# pong.net
KiCad netlist of a schematic drawn in EAGLE
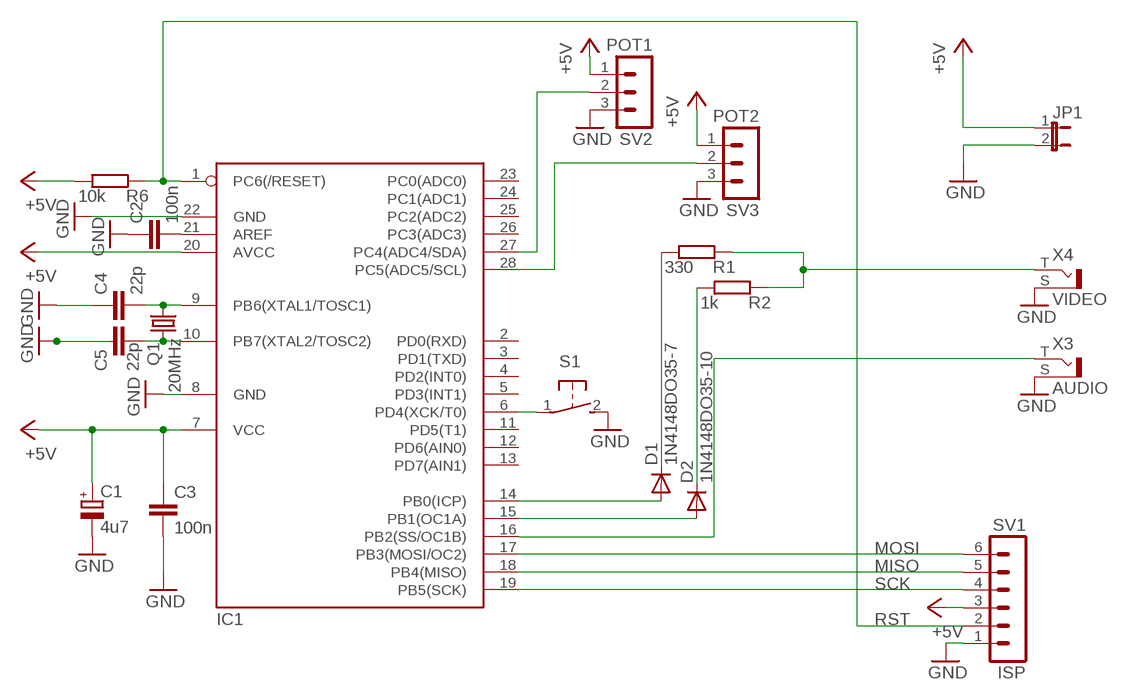
[diagram p0: schematic, sheet 1]

(export (version "E")
  (design (tool "Eeschema 10.0.6"))
  (components
    (comp (ref "C1")
      (value "4u7")
      (footprint "eagle-import:TT5D7")
      (libsource (lib "eagle-import") (part "CPOL-EUTT5D7"))
    )
    (comp (ref "C2")
      (value "100n")
      (footprint "eagle-import:C025-024X044")
      (libsource (lib "eagle-import") (part "C-EU025-024X044"))
    )
    (comp (ref "C3")
      (value "100n")
      (footprint "eagle-import:C025-024X044")
      (libsource (lib "eagle-import") (part "C-EU025-024X044"))
    )
    (comp (ref "C4")
      (value "22p")
      (footprint "eagle-import:C025-024X044")
      (libsource (lib "eagle-import") (part "C-EU025-024X044"))
    )
    (comp (ref "C5")
      (value "22p")
      (footprint "eagle-import:C050-025X075")
      (libsource (lib "eagle-import") (part "C-EU050-025X075"))
    )
    (comp (ref "D1")
      (value "1N4148DO35-7")
      (footprint "eagle-import:DO35-7")
      (libsource (lib "eagle-import") (part "1N4148DO35-7"))
    )
    (comp (ref "D2")
      (value "1N4148DO35-10")
      (footprint "eagle-import:DO35-10")
      (libsource (lib "eagle-import") (part "1N4148DO35-10"))
    )
    (comp (ref "IC1")
      (value "MEGA8-P")
      (footprint "eagle-import:DIL28-3")
      (libsource (lib "eagle-import") (part "MEGA8-P"))
    )
    (comp (ref "JP1")
      (value "JP1E")
      (footprint "eagle-import:JP1")
      (libsource (lib "eagle-import") (part "JP1E"))
    )
    (comp (ref "Q1")
      (value "20MHz")
      (footprint "eagle-import:TC26V")
      (libsource (lib "eagle-import") (part "CRYSTALTC26V"))
    )
    (comp (ref "R1")
      (value "330")
      (footprint "eagle-import:0204_5")
      (libsource (lib "eagle-import") (part "R-EU_0204/5"))
    )
    (comp (ref "R2")
      (value "1k")
      (footprint "eagle-import:0204_7")
      (libsource (lib "eagle-import") (part "R-EU_0204/7"))
    )
    (comp (ref "R6")
      (value "10k")
      (footprint "eagle-import:0207_15")
      (libsource (lib "eagle-import") (part "R-EU_0207/15"))
    )
    (comp (ref "S1")
      (value "31-XX")
      (footprint "eagle-import:B3F-31XX")
      (fields (field (name "MPN") "B3F-3100"))
      (libsource (lib "eagle-import") (part "31-XX"))
    )
    (comp (ref "SV1")
      (value "ISP")
      (footprint "eagle-import:MA06-1")
      (libsource (lib "eagle-import") (part "MA06-1"))
    )
    (comp (ref "SV2")
      (value "POT1")
      (footprint "eagle-import:MA03-1")
      (libsource (lib "eagle-import") (part "MA03-1"))
    )
    (comp (ref "SV3")
      (value "POT2")
      (footprint "eagle-import:MA03-1")
      (libsource (lib "eagle-import") (part "MA03-1"))
    )
    (comp (ref "X3")
      (value "AUDIO")
      (footprint "eagle-import:WBTOR1")
      (fields (field (name "MPN") "WBTOR 1 BLACK"))
      (libsource (lib "eagle-import") (part "WBTOR1"))
    )
    (comp (ref "X4")
      (value "VIDEO")
      (footprint "eagle-import:WBTOR1")
      (fields (field (name "MPN") "WBTOR 1 BLACK"))
      (libsource (lib "eagle-import") (part "WBTOR1"))
    )
  )
  (nets
    (net (code "1") (name "+5V") (class "Default")
      (node (ref "C1") (pin "+") (pinfunction "+_+") (pintype "passive"))
      (node (ref "C3") (pin "1") (pinfunction "1_1") (pintype "passive"))
      (node (ref "IC1") (pin "20") (pinfunction "AVCC_20") (pintype "power_in"))
      (node (ref "IC1") (pin "7") (pinfunction "VCC_7") (pintype "power_in"))
      (node (ref "JP1") (pin "1") (pinfunction "1_1") (pintype "passive"))
      (node (ref "R6") (pin "1") (pinfunction "1_1") (pintype "passive"))
      (node (ref "SV1") (pin "3") (pinfunction "3_3") (pintype "passive"))
      (node (ref "SV2") (pin "1") (pinfunction "1_1") (pintype "passive"))
      (node (ref "SV3") (pin "1") (pinfunction "1_1") (pintype "passive"))
    )
    (net (code "2") (name "/MISO") (class "Default")
      (node (ref "IC1") (pin "18") (pinfunction "PB4(MISO)_18") (pintype "bidirectional"))
      (node (ref "SV1") (pin "5") (pinfunction "5_5") (pintype "passive"))
    )
    (net (code "3") (name "/MOSI") (class "Default")
      (node (ref "IC1") (pin "17") (pinfunction "PB3(MOSI/OC2)_17") (pintype "bidirectional"))
      (node (ref "SV1") (pin "6") (pinfunction "6_6") (pintype "passive"))
    )
    (net (code "4") (name "/RST") (class "Default")
      (node (ref "IC1") (pin "1") (pinfunction "PC6(/RESET)_1") (pintype "bidirectional"))
      (node (ref "R6") (pin "2") (pinfunction "2_2") (pintype "passive"))
      (node (ref "SV1") (pin "2") (pinfunction "2_2") (pintype "passive"))
    )
    (net (code "5") (name "/SCK") (class "Default")
      (node (ref "IC1") (pin "19") (pinfunction "PB5(SCK)_19") (pintype "bidirectional"))
      (node (ref "SV1") (pin "4") (pinfunction "4_4") (pintype "passive"))
    )
    (net (code "6") (name "GND") (class "Default")
      (node (ref "C1") (pin "-") (pinfunction "-_-") (pintype "passive"))
      (node (ref "C2") (pin "1") (pinfunction "1_1") (pintype "passive"))
      (node (ref "C3") (pin "2") (pinfunction "2_2") (pintype "passive"))
      (node (ref "C4") (pin "1") (pinfunction "1_1") (pintype "passive"))
      (node (ref "C5") (pin "1") (pinfunction "1_1") (pintype "passive"))
      (node (ref "IC1") (pin "22") (pinfunction "GND_22") (pintype "power_in"))
      (node (ref "IC1") (pin "8") (pinfunction "GND_8") (pintype "power_in"))
      (node (ref "JP1") (pin "2") (pinfunction "2_2") (pintype "passive"))
      (node (ref "S1") (pin "2") (pinfunction "S_2") (pintype "passive"))
      (node (ref "SV1") (pin "1") (pinfunction "1_1") (pintype "passive"))
      (node (ref "SV2") (pin "3") (pinfunction "3_3") (pintype "passive"))
      (node (ref "SV3") (pin "3") (pinfunction "3_3") (pintype "passive"))
      (node (ref "X3") (pin "S") (pinfunction "S_S") (pintype "passive"))
      (node (ref "X4") (pin "S") (pinfunction "S_S") (pintype "passive"))
    )
    (net (code "7") (name "Net-(D1-PadC)") (class "Default")
      (node (ref "D1") (pin "C") (pinfunction "C_C") (pintype "passive"))
      (node (ref "R1") (pin "1") (pinfunction "1_1") (pintype "passive"))
    )
    (net (code "8") (name "Net-(D2-PadC)") (class "Default")
      (node (ref "D2") (pin "C") (pinfunction "C_C") (pintype "passive"))
      (node (ref "R2") (pin "1") (pinfunction "1_1") (pintype "passive"))
    )
    (net (code "9") (name "Net-(IC1-AREF)") (class "Default")
      (node (ref "C2") (pin "2") (pinfunction "2_2") (pintype "passive"))
      (node (ref "IC1") (pin "21") (pinfunction "AREF_21") (pintype "passive"))
    )
    (net (code "10") (name "Net-(IC1-PB0(ICP))") (class "Default")
      (node (ref "D1") (pin "A") (pinfunction "A_A") (pintype "passive"))
      (node (ref "IC1") (pin "14") (pinfunction "PB0(ICP)_14") (pintype "bidirectional"))
    )
    (net (code "11") (name "Net-(IC1-PB1(OC1A))") (class "Default")
      (node (ref "D2") (pin "A") (pinfunction "A_A") (pintype "passive"))
      (node (ref "IC1") (pin "15") (pinfunction "PB1(OC1A)_15") (pintype "bidirectional"))
    )
    (net (code "12") (name "Net-(IC1-PB2(SS{slash}OC1B))") (class "Default")
      (node (ref "IC1") (pin "16") (pinfunction "PB2(SS/OC1B)_16") (pintype "bidirectional"))
      (node (ref "X3") (pin "T") (pinfunction "T_T") (pintype "passive"))
    )
    (net (code "13") (name "Net-(IC1-PB6(XTAL1{slash}TOSC1))") (class "Default")
      (node (ref "C4") (pin "2") (pinfunction "2_2") (pintype "passive"))
      (node (ref "IC1") (pin "9") (pinfunction "PB6(XTAL1/TOSC1)_9") (pintype "bidirectional"))
      (node (ref "Q1") (pin "2") (pinfunction "2_2") (pintype "passive"))
    )
    (net (code "14") (name "Net-(IC1-PB7(XTAL2{slash}TOSC2))") (class "Default")
      (node (ref "C5") (pin "2") (pinfunction "2_2") (pintype "passive"))
      (node (ref "IC1") (pin "10") (pinfunction "PB7(XTAL2/TOSC2)_10") (pintype "bidirectional"))
      (node (ref "Q1") (pin "1") (pinfunction "1_1") (pintype "passive"))
    )
    (net (code "15") (name "Net-(IC1-PC4(ADC4{slash}SDA))") (class "Default")
      (node (ref "IC1") (pin "27") (pinfunction "PC4(ADC4/SDA)_27") (pintype "bidirectional"))
      (node (ref "SV2") (pin "2") (pinfunction "2_2") (pintype "passive"))
    )
    (net (code "16") (name "Net-(IC1-PC5(ADC5{slash}SCL))") (class "Default")
      (node (ref "IC1") (pin "28") (pinfunction "PC5(ADC5/SCL)_28") (pintype "bidirectional"))
      (node (ref "SV3") (pin "2") (pinfunction "2_2") (pintype "passive"))
    )
    (net (code "17") (name "Net-(IC1-PD4(XCK{slash}T0))") (class "Default")
      (node (ref "IC1") (pin "6") (pinfunction "PD4(XCK/T0)_6") (pintype "bidirectional"))
      (node (ref "S1") (pin "1") (pinfunction "P_1") (pintype "passive"))
    )
    (net (code "18") (name "Net-(R1-Pad2)") (class "Default")
      (node (ref "R1") (pin "2") (pinfunction "2_2") (pintype "passive"))
      (node (ref "R2") (pin "2") (pinfunction "2_2") (pintype "passive"))
      (node (ref "X4") (pin "T") (pinfunction "T_T") (pintype "passive"))
    )
    (net (code "19") (name "unconnected-(IC1-PC0(ADC0)-Pad23)") (class "Default")
      (node (ref "IC1") (pin "23") (pinfunction "PC0(ADC0)_23") (pintype "bidirectional"))
    )
    (net (code "20") (name "unconnected-(IC1-PC1(ADC1)-Pad24)") (class "Default")
      (node (ref "IC1") (pin "24") (pinfunction "PC1(ADC1)_24") (pintype "bidirectional"))
    )
    (net (code "21") (name "unconnected-(IC1-PC2(ADC2)-Pad25)") (class "Default")
      (node (ref "IC1") (pin "25") (pinfunction "PC2(ADC2)_25") (pintype "bidirectional"))
    )
    (net (code "22") (name "unconnected-(IC1-PC3(ADC3)-Pad26)") (class "Default")
      (node (ref "IC1") (pin "26") (pinfunction "PC3(ADC3)_26") (pintype "bidirectional"))
    )
    (net (code "23") (name "unconnected-(IC1-PD0(RXD)-Pad2)") (class "Default")
      (node (ref "IC1") (pin "2") (pinfunction "PD0(RXD)_2") (pintype "bidirectional"))
    )
    (net (code "24") (name "unconnected-(IC1-PD1(TXD)-Pad3)") (class "Default")
      (node (ref "IC1") (pin "3") (pinfunction "PD1(TXD)_3") (pintype "bidirectional"))
    )
    (net (code "25") (name "unconnected-(IC1-PD2(INT0)-Pad4)") (class "Default")
      (node (ref "IC1") (pin "4") (pinfunction "PD2(INT0)_4") (pintype "bidirectional"))
    )
    (net (code "26") (name "unconnected-(IC1-PD3(INT1)-Pad5)") (class "Default")
      (node (ref "IC1") (pin "5") (pinfunction "PD3(INT1)_5") (pintype "bidirectional"))
    )
    (net (code "27") (name "unconnected-(IC1-PD5(T1)-Pad11)") (class "Default")
      (node (ref "IC1") (pin "11") (pinfunction "PD5(T1)_11") (pintype "bidirectional"))
    )
    (net (code "28") (name "unconnected-(IC1-PD6(AIN0)-Pad12)") (class "Default")
      (node (ref "IC1") (pin "12") (pinfunction "PD6(AIN0)_12") (pintype "bidirectional"))
    )
    (net (code "29") (name "unconnected-(IC1-PD7(AIN1)-Pad13)") (class "Default")
      (node (ref "IC1") (pin "13") (pinfunction "PD7(AIN1)_13") (pintype "bidirectional"))
    )
  )
)
